# escape-room-riddle-box_2020-11-22_15-05-.net
KiCad netlist of a schematic drawn in Altium Designer
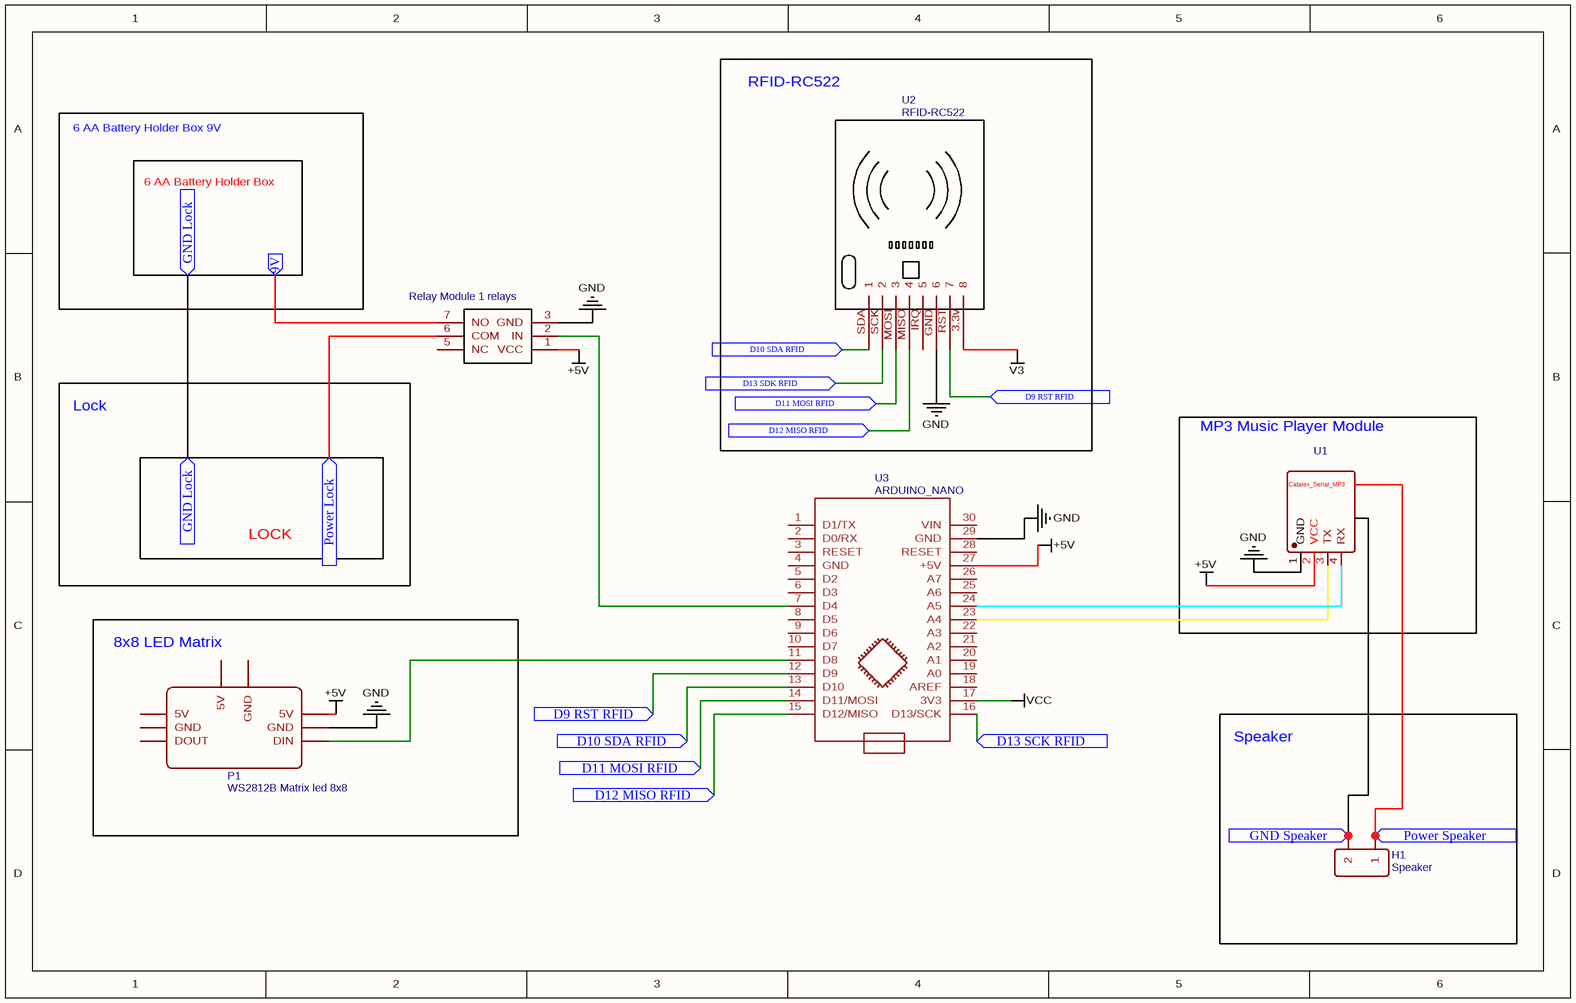
[diagram p0: escape-room-riddle-box_2020-11-22_15-05-28.schdoc]

(export (version "E")
  (design (tool "Eeschema 10.0.6"))
  (components
    (comp (ref "H1")
      (value "Speaker")
      (fields
        (field (name "BOM_MANUFACTURER PART") "826629-2")
        (field (name "BOM_SUPPLIER PART") "C86471")
        (field (name "CONTRIBUTOR") "SmartPrototype")
      )
      (libsource (lib "altium-import") (part "root_3_Speaker_"))
    )
    (comp (ref "P1")
      (value "WS2812B Matrix led 8x8")
      (fields (field (name "CONTRIBUTOR") "Flavio Bontà"))
      (libsource (lib "altium-import") (part "root_0_WS2812B Matrix led 8x8_"))
    )
    (comp (ref "U1")
      (value "Catalex_Serial_MP3")
      (fields
        (field (name "BOM_MANUFACTURER PART") "Catalex_Serial_MP3_Board")
        (field (name "CONTRIBUTOR") "davidsamuellevin")
      )
      (libsource (lib "altium-import") (part "root_1_Catalex_Serial_MP3_"))
    )
    (comp (ref "U2")
      (value "RFID-RC522")
      (fields (field (name "BOM_MANUFACTURER PART") "NXP") (field (name "CONTRIBUTOR") "dr.mr.beast"))
      (libsource (lib "altium-import") (part "root_0_RFID-RC522_"))
    )
    (comp (ref "U3") (value "ARDUINO_NANO") (libsource (lib "altium-import") (part "root_0_ARDUINO_NANO_")))
    (comp (ref "U4")
      (value "Relay Module 1 relays")
      (fields (field (name "CONTRIBUTOR") "roman555"))
      (libsource (lib "altium-import") (part "root_1_Relay Module 1 relays_"))
    )
  )
  (nets
    (net (code "1") (name "+5V") (class "Default")
      (node (ref "P1") (pin "3") (pinfunction "5V_3") (pintype "passive"))
      (node (ref "U1") (pin "2") (pinfunction "VCC_2") (pintype "passive"))
      (node (ref "U3") (pin "27") (pinfunction "+5V_27") (pintype "passive"))
      (node (ref "U4") (pin "1") (pinfunction "VCC_1") (pintype "passive"))
    )
    (net (code "2") (name "/9V") (class "Default")
      (node (ref "U4") (pin "7") (pinfunction "NO_7") (pintype "passive"))
    )
    (net (code "3") (name "/D9 RST RFID") (class "Default")
      (node (ref "U2") (pin "RST") (pinfunction "7_RST") (pintype "passive"))
      (node (ref "U3") (pin "12") (pinfunction "D9_12") (pintype "passive"))
    )
    (net (code "4") (name "/D10 SDA RFID") (class "Default")
      (node (ref "U2") (pin "SDA") (pinfunction "1_SDA") (pintype "passive"))
      (node (ref "U3") (pin "13") (pinfunction "D10_13") (pintype "passive"))
    )
    (net (code "5") (name "/D11 MOSI RFID") (class "Default")
      (node (ref "U2") (pin "MOSI") (pinfunction "3_MOSI") (pintype "passive"))
      (node (ref "U3") (pin "14") (pinfunction "D11/MOSI_14") (pintype "passive"))
    )
    (net (code "6") (name "/D12 MISO RFID") (class "Default")
      (node (ref "U2") (pin "MISO") (pinfunction "4_MISO") (pintype "passive"))
      (node (ref "U3") (pin "15") (pinfunction "D12/MISO_15") (pintype "passive"))
    )
    (net (code "7") (name "/D13 SCK RFID") (class "Default")
      (node (ref "U3") (pin "16") (pinfunction "D13/SCK_16") (pintype "passive"))
    )
    (net (code "8") (name "/D13 SDK RFID") (class "Default")
      (node (ref "U2") (pin "SCK") (pinfunction "2_SCK") (pintype "passive"))
    )
    (net (code "10") (name "/GND Speaker") (class "Default")
      (node (ref "H1") (pin "2") (pinfunction "2_2") (pintype "passive"))
    )
    (net (code "11") (name "/Power Lock") (class "Default")
      (node (ref "U4") (pin "6") (pinfunction "COM_6") (pintype "passive"))
    )
    (net (code "12") (name "/Power Speaker") (class "Default")
      (node (ref "H1") (pin "1") (pinfunction "1_1") (pintype "passive"))
    )
    (net (code "13") (name "GND") (class "Default")
      (node (ref "P1") (pin "2") (pinfunction "GND_2") (pintype "passive"))
      (node (ref "U1") (pin "1") (pinfunction "GND_1") (pintype "passive"))
      (node (ref "U2") (pin "GND") (pinfunction "6_GND") (pintype "passive"))
      (node (ref "U3") (pin "29") (pinfunction "GND_29") (pintype "passive"))
      (node (ref "U4") (pin "3") (pinfunction "GND_3") (pintype "passive"))
    )
    (net (code "14") (name "Net-(P1-DIN)") (class "Default")
      (node (ref "P1") (pin "1") (pinfunction "DIN_1") (pintype "passive"))
      (node (ref "U3") (pin "11") (pinfunction "D8_11") (pintype "passive"))
    )
    (net (code "15") (name "Net-(U1-RX)") (class "Default")
      (node (ref "U1") (pin "4") (pinfunction "RX_4") (pintype "passive"))
      (node (ref "U3") (pin "24") (pinfunction "A5_24") (pintype "passive"))
    )
    (net (code "16") (name "Net-(U1-TX)") (class "Default")
      (node (ref "U1") (pin "3") (pinfunction "TX_3") (pintype "passive"))
      (node (ref "U3") (pin "23") (pinfunction "A4_23") (pintype "passive"))
    )
    (net (code "17") (name "Net-(U3-D4)") (class "Default")
      (node (ref "U3") (pin "7") (pinfunction "D4_7") (pintype "passive"))
      (node (ref "U4") (pin "2") (pinfunction "IN_2") (pintype "passive"))
    )
    (net (code "18") (name "V3") (class "Default")
      (node (ref "U2") (pin "3.3v") (pinfunction "8_3.3v") (pintype "passive"))
    )
    (net (code "19") (name "VCC") (class "Default")
      (node (ref "U3") (pin "17") (pinfunction "3V3_17") (pintype "passive"))
    )
    (net (code "20") (name "unconnected-(P1-5V-Pad6)") (class "Default")
      (node (ref "P1") (pin "6") (pinfunction "5V_6") (pintype "passive"))
    )
    (net (code "21") (name "unconnected-(P1-5V-Pad7)") (class "Default")
      (node (ref "P1") (pin "7") (pinfunction "5V_7") (pintype "passive"))
    )
    (net (code "22") (name "unconnected-(P1-DOUT-Pad4)") (class "Default")
      (node (ref "P1") (pin "4") (pinfunction "DOUT_4") (pintype "passive"))
    )
    (net (code "23") (name "unconnected-(P1-GND-Pad5)") (class "Default")
      (node (ref "P1") (pin "5") (pinfunction "GND_5") (pintype "passive"))
    )
    (net (code "24") (name "unconnected-(P1-GND-Pad8)") (class "Default")
      (node (ref "P1") (pin "8") (pinfunction "GND_8") (pintype "passive"))
    )
    (net (code "25") (name "unconnected-(U2-5-PadIRQ)") (class "Default")
      (node (ref "U2") (pin "IRQ") (pinfunction "5_IRQ") (pintype "passive"))
    )
    (net (code "26") (name "unconnected-(U3-A0-Pad19)") (class "Default")
      (node (ref "U3") (pin "19") (pinfunction "A0_19") (pintype "passive"))
    )
    (net (code "27") (name "unconnected-(U3-A1-Pad20)") (class "Default")
      (node (ref "U3") (pin "20") (pinfunction "A1_20") (pintype "passive"))
    )
    (net (code "28") (name "unconnected-(U3-A2-Pad21)") (class "Default")
      (node (ref "U3") (pin "21") (pinfunction "A2_21") (pintype "passive"))
    )
    (net (code "29") (name "unconnected-(U3-A3-Pad22)") (class "Default")
      (node (ref "U3") (pin "22") (pinfunction "A3_22") (pintype "passive"))
    )
    (net (code "30") (name "unconnected-(U3-A6-Pad25)") (class "Default")
      (node (ref "U3") (pin "25") (pinfunction "A6_25") (pintype "passive"))
    )
    (net (code "31") (name "unconnected-(U3-A7-Pad26)") (class "Default")
      (node (ref "U3") (pin "26") (pinfunction "A7_26") (pintype "passive"))
    )
    (net (code "32") (name "unconnected-(U3-AREF-Pad18)") (class "Default")
      (node (ref "U3") (pin "18") (pinfunction "AREF_18") (pintype "passive"))
    )
    (net (code "33") (name "unconnected-(U3-D0{slash}RX-Pad2)") (class "Default")
      (node (ref "U3") (pin "2") (pinfunction "D0/RX_2") (pintype "passive"))
    )
    (net (code "34") (name "unconnected-(U3-D1{slash}TX-Pad1)") (class "Default")
      (node (ref "U3") (pin "1") (pinfunction "D1/TX_1") (pintype "passive"))
    )
    (net (code "35") (name "unconnected-(U3-D2-Pad5)") (class "Default")
      (node (ref "U3") (pin "5") (pinfunction "D2_5") (pintype "passive"))
    )
    (net (code "36") (name "unconnected-(U3-D3-Pad6)") (class "Default")
      (node (ref "U3") (pin "6") (pinfunction "D3_6") (pintype "passive"))
    )
    (net (code "37") (name "unconnected-(U3-D5-Pad8)") (class "Default")
      (node (ref "U3") (pin "8") (pinfunction "D5_8") (pintype "passive"))
    )
    (net (code "38") (name "unconnected-(U3-D6-Pad9)") (class "Default")
      (node (ref "U3") (pin "9") (pinfunction "D6_9") (pintype "passive"))
    )
    (net (code "39") (name "unconnected-(U3-D7-Pad10)") (class "Default")
      (node (ref "U3") (pin "10") (pinfunction "D7_10") (pintype "passive"))
    )
    (net (code "40") (name "unconnected-(U3-GND-Pad4)") (class "Default")
      (node (ref "U3") (pin "4") (pinfunction "GND_4") (pintype "passive"))
    )
    (net (code "41") (name "unconnected-(U3-RESET-Pad3)") (class "Default")
      (node (ref "U3") (pin "3") (pinfunction "RESET_3") (pintype "passive"))
    )
    (net (code "42") (name "unconnected-(U3-RESET-Pad28)") (class "Default")
      (node (ref "U3") (pin "28") (pinfunction "RESET_28") (pintype "passive"))
    )
    (net (code "43") (name "unconnected-(U3-VIN-Pad30)") (class "Default")
      (node (ref "U3") (pin "30") (pinfunction "VIN_30") (pintype "passive"))
    )
    (net (code "44") (name "unconnected-(U4-NC-Pad5)") (class "Default")
      (node (ref "U4") (pin "5") (pinfunction "NC_5") (pintype "passive"))
    )
  )
)
